# 02_COM.net
KiCad netlist of a schematic drawn in Altium Designer
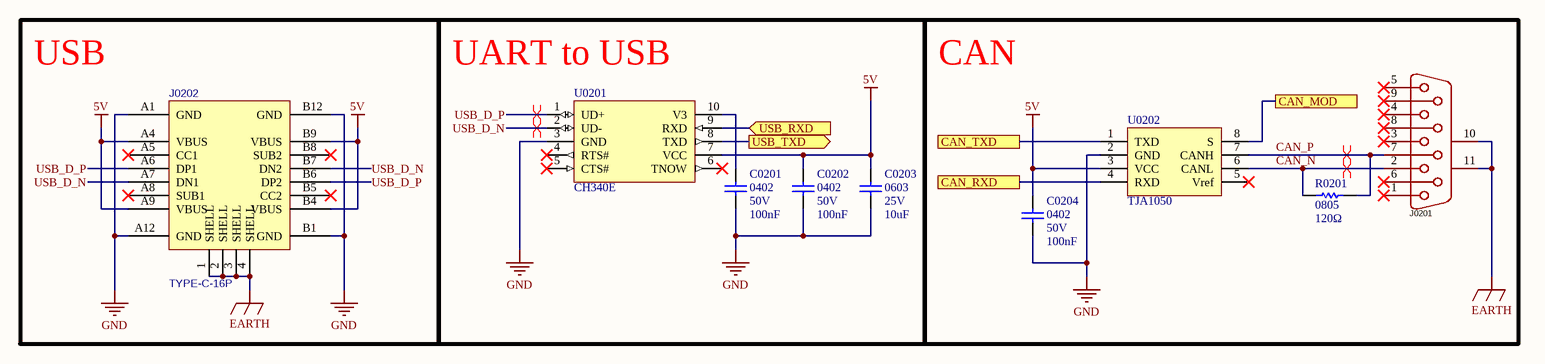
[diagram p0: 02_COM.SchDoc]

(export (version "E")
  (design (tool "Eeschema 10.0.6"))
  (components
    (comp (ref "C0201")
      (value "Cap")
      (footprint "C0402")
      (fields (field (name "SIZE") "0402") (field (name "VOLT") "50V") (field (name "CAP") "100nF"))
      (libsource (lib "LCR") (part "Cap"))
    )
    (comp (ref "C0202")
      (value "Cap")
      (footprint "C0402")
      (fields (field (name "SIZE") "0402") (field (name "VOLT") "50V") (field (name "CAP") "100nF"))
      (libsource (lib "LCR") (part "Cap"))
    )
    (comp (ref "C0203")
      (value "Cap")
      (footprint "C0603")
      (fields (field (name "SIZE") "0603") (field (name "VOLT") "25V") (field (name "CAP") "10uF"))
      (libsource (lib "LCR") (part "Cap"))
    )
    (comp (ref "C0204")
      (value "Cap")
      (footprint "C0402")
      (fields (field (name "SIZE") "0402") (field (name "VOLT") "50V") (field (name "CAP") "100nF"))
      (libsource (lib "LCR") (part "Cap"))
    )
    (comp (ref "J0201")
      (value "DB9P")
      (footprint "DB9P")
      (fields (field (name "MANUFACTURER") "Amphenol") (field (name "MANUFACTURER PART") "ID09S33E4GV00LF"))
      (libsource (lib "Interface") (part "DB9P"))
    )
    (comp (ref "J0202")
      (value "TYPE-C-16P")
      (footprint "USB-C_16P")
      (fields
        (field (name "BOM_SUPPLIER PART") "C709357")
        (field (name "BOM_MANUFACTURER PART") "KH-TYPE-C-16P")
        (field (name "CONTRIBUTOR") "LCSC")
      )
      (libsource (lib "Interface") (part "USB-C-16P"))
    )
    (comp (ref "R0201")
      (value "RES")
      (footprint "R0805")
      (description "电阻")
      (fields (field (name "SIZE") "0805") (field (name "RES") "120Ω"))
      (libsource (lib "LCR") (part "RES"))
    )
    (comp (ref "U0201")
      (value "CH340E")
      (footprint "MSOP10")
      (description "USB to TTL Serial / UART")
      (libsource (lib "ComIC") (part "CH340E"))
    )
    (comp (ref "U0202")
      (value "TJA1050")
      (footprint "SOIC8_L W=3.9mm")
      (libsource (lib "ComIC") (part "TJA1050"))
    )
  )
  (nets
    (net (code "1") (name "/CAN_MOD") (class "Default")
      (node (ref "U0202") (pin "8") (pinfunction "S_8") (pintype "passive"))
    )
    (net (code "2") (name "/CAN_N") (class "Default")
      (node (ref "J0201") (pin "2") (pinfunction "2_2") (pintype "passive"))
      (node (ref "R0201") (pin "2") (pinfunction "2_2") (pintype "passive"))
      (node (ref "U0202") (pin "6") (pinfunction "CANL_6") (pintype "passive"))
    )
    (net (code "3") (name "/CAN_P") (class "Default")
      (node (ref "J0201") (pin "7") (pinfunction "7_7") (pintype "passive"))
      (node (ref "R0201") (pin "1") (pinfunction "1_1") (pintype "passive"))
      (node (ref "U0202") (pin "7") (pinfunction "CANH_7") (pintype "passive"))
    )
    (net (code "4") (name "/CAN_RXD") (class "Default")
      (node (ref "U0202") (pin "4") (pinfunction "RXD_4") (pintype "passive"))
    )
    (net (code "5") (name "/CAN_TXD") (class "Default")
      (node (ref "U0202") (pin "1") (pinfunction "TXD_1") (pintype "passive"))
    )
    (net (code "6") (name "/USB_D_N") (class "Default")
      (node (ref "J0202") (pin "A7") (pinfunction "DN1_A7") (pintype "passive"))
      (node (ref "J0202") (pin "B7") (pinfunction "DN2_B7") (pintype "passive"))
      (node (ref "U0201") (pin "2") (pinfunction "UD-_2") (pintype "bidirectional"))
    )
    (net (code "7") (name "/USB_D_P") (class "Default")
      (node (ref "J0202") (pin "A6") (pinfunction "DP1_A6") (pintype "passive"))
      (node (ref "J0202") (pin "B6") (pinfunction "DP2_B6") (pintype "passive"))
      (node (ref "U0201") (pin "1") (pinfunction "UD+_1") (pintype "bidirectional"))
    )
    (net (code "8") (name "/USB_RXD") (class "Default")
      (node (ref "U0201") (pin "9") (pinfunction "RXD_9") (pintype "input"))
    )
    (net (code "9") (name "/USB_TXD") (class "Default")
      (node (ref "U0201") (pin "8") (pinfunction "TXD_8") (pintype "output"))
    )
    (net (code "10") (name "5V") (class "Default")
      (node (ref "C0202") (pin "2") (pinfunction "2_2") (pintype "passive"))
      (node (ref "C0203") (pin "2") (pinfunction "2_2") (pintype "passive"))
      (node (ref "C0204") (pin "2") (pinfunction "2_2") (pintype "passive"))
      (node (ref "J0202") (pin "A4") (pinfunction "VBUS_A4") (pintype "passive"))
      (node (ref "J0202") (pin "A9") (pinfunction "VBUS_A9") (pintype "passive"))
      (node (ref "J0202") (pin "B4") (pinfunction "VBUS_B4") (pintype "passive"))
      (node (ref "J0202") (pin "B9") (pinfunction "VBUS_B9") (pintype "passive"))
      (node (ref "U0201") (pin "7") (pinfunction "VCC_7") (pintype "power_in"))
      (node (ref "U0202") (pin "3") (pinfunction "VCC_3") (pintype "passive"))
    )
    (net (code "11") (name "EARTH") (class "Default")
      (node (ref "J0201") (pin "10") (pinfunction "MH1_10") (pintype "passive"))
      (node (ref "J0201") (pin "11") (pinfunction "MH2_11") (pintype "passive"))
      (node (ref "J0202") (pin "1") (pinfunction "SHELL_1") (pintype "passive"))
      (node (ref "J0202") (pin "2") (pinfunction "SHELL_2") (pintype "passive"))
      (node (ref "J0202") (pin "3") (pinfunction "SHELL_3") (pintype "passive"))
      (node (ref "J0202") (pin "4") (pinfunction "SHELL_4") (pintype "passive"))
    )
    (net (code "12") (name "GND") (class "Default")
      (node (ref "C0201") (pin "1") (pinfunction "1_1") (pintype "passive"))
      (node (ref "C0202") (pin "1") (pinfunction "1_1") (pintype "passive"))
      (node (ref "C0203") (pin "1") (pinfunction "1_1") (pintype "passive"))
      (node (ref "C0204") (pin "1") (pinfunction "1_1") (pintype "passive"))
      (node (ref "J0202") (pin "A1") (pinfunction "GND_A1") (pintype "passive"))
      (node (ref "J0202") (pin "A12") (pinfunction "GND_A12") (pintype "passive"))
      (node (ref "J0202") (pin "B1") (pinfunction "GND_B1") (pintype "passive"))
      (node (ref "J0202") (pin "B12") (pinfunction "GND_B12") (pintype "passive"))
      (node (ref "U0201") (pin "3") (pinfunction "GND_3") (pintype "power_in"))
      (node (ref "U0202") (pin "2") (pinfunction "GND_2") (pintype "passive"))
    )
    (net (code "13") (name "Net-(U0201-V3)") (class "Default")
      (node (ref "C0201") (pin "2") (pinfunction "2_2") (pintype "passive"))
      (node (ref "U0201") (pin "10") (pinfunction "V3_10") (pintype "power_in"))
    )
    (net (code "14") (name "unconnected-(J0201-Pad1)") (class "Default")
      (node (ref "J0201") (pin "1") (pinfunction "1_1") (pintype "passive+no_connect"))
    )
    (net (code "15") (name "unconnected-(J0201-Pad3)") (class "Default")
      (node (ref "J0201") (pin "3") (pinfunction "3_3") (pintype "passive+no_connect"))
    )
    (net (code "16") (name "unconnected-(J0201-Pad4)") (class "Default")
      (node (ref "J0201") (pin "4") (pinfunction "4_4") (pintype "passive+no_connect"))
    )
    (net (code "17") (name "unconnected-(J0201-Pad5)") (class "Default")
      (node (ref "J0201") (pin "5") (pinfunction "5_5") (pintype "passive+no_connect"))
    )
    (net (code "18") (name "unconnected-(J0201-Pad6)") (class "Default")
      (node (ref "J0201") (pin "6") (pinfunction "6_6") (pintype "passive+no_connect"))
    )
    (net (code "19") (name "unconnected-(J0201-Pad8)") (class "Default")
      (node (ref "J0201") (pin "8") (pinfunction "8_8") (pintype "passive+no_connect"))
    )
    (net (code "20") (name "unconnected-(J0201-Pad9)") (class "Default")
      (node (ref "J0201") (pin "9") (pinfunction "9_9") (pintype "passive+no_connect"))
    )
    (net (code "21") (name "unconnected-(J0202-CC1-PadA5)") (class "Default")
      (node (ref "J0202") (pin "A5") (pinfunction "CC1_A5") (pintype "passive+no_connect"))
    )
    (net (code "22") (name "unconnected-(J0202-CC2-PadB5)") (class "Default")
      (node (ref "J0202") (pin "B5") (pinfunction "CC2_B5") (pintype "passive+no_connect"))
    )
    (net (code "23") (name "unconnected-(J0202-SUB1-PadA8)") (class "Default")
      (node (ref "J0202") (pin "A8") (pinfunction "SUB1_A8") (pintype "passive+no_connect"))
    )
    (net (code "24") (name "unconnected-(J0202-SUB2-PadB8)") (class "Default")
      (node (ref "J0202") (pin "B8") (pinfunction "SUB2_B8") (pintype "passive+no_connect"))
    )
    (net (code "25") (name "unconnected-(U0201-CTS#-Pad5)") (class "Default")
      (node (ref "U0201") (pin "5") (pinfunction "CTS#_5") (pintype "input+no_connect"))
    )
    (net (code "26") (name "unconnected-(U0201-RTS#-Pad4)") (class "Default")
      (node (ref "U0201") (pin "4") (pinfunction "RTS#_4") (pintype "output+no_connect"))
    )
    (net (code "27") (name "unconnected-(U0201-TNOW-Pad6)") (class "Default")
      (node (ref "U0201") (pin "6") (pinfunction "TNOW_6") (pintype "output+no_connect"))
    )
    (net (code "28") (name "unconnected-(U0202-Vref-Pad5)") (class "Default")
      (node (ref "U0202") (pin "5") (pinfunction "Vref_5") (pintype "passive+no_connect"))
    )
  )
)
